# SUPPLY.net
KiCad netlist of a schematic drawn in Altium Designer
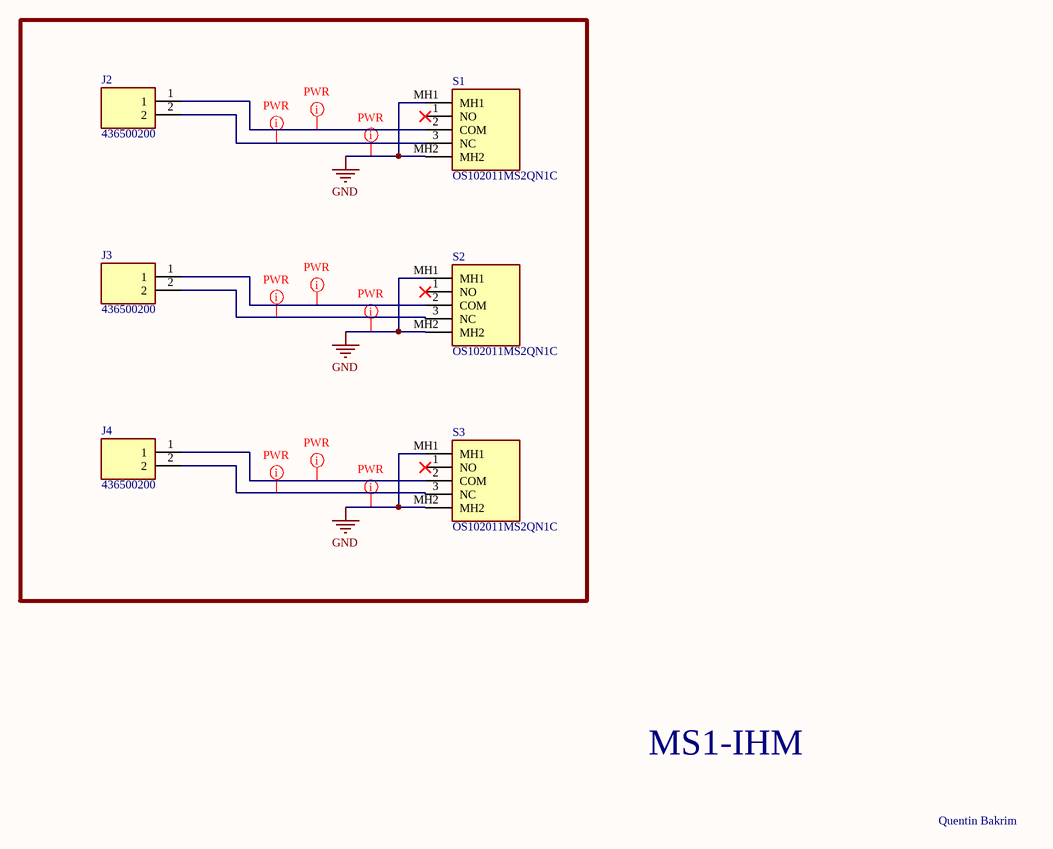
[diagram p0: SUPPLY.SchDoc]

(export (version "E")
  (design (tool "Eeschema 10.0.6"))
  (components
    (comp (ref "J2")
      (value "436500200")
      (footprint "436500200:MOLEX_436500200")
      (fields (field (name "MF") "{'manufacturer': u'Molex'}"))
      (libsource (lib "*") (part "436500200"))
    )
    (comp (ref "J3")
      (value "436500200")
      (footprint "436500200:MOLEX_436500200")
      (fields (field (name "MF") "{'manufacturer': u'Molex'}"))
      (libsource (lib "*") (part "436500200"))
    )
    (comp (ref "J4")
      (value "436500200")
      (footprint "436500200:MOLEX_436500200")
      (fields (field (name "MF") "{'manufacturer': u'Molex'}"))
      (libsource (lib "*") (part "436500200"))
    )
    (comp (ref "S1")
      (value "OS102011MS2QN1C")
      (footprint "SamacSys:OS102011MS2QN1C")
      (description "Switch")
      (fields (field (name "MOUSER PART NUMBER") "611-OS102011MS2QN1C"))
      (libsource (lib "*") (part "OS102011MS2QN1C"))
    )
    (comp (ref "S2")
      (value "OS102011MS2QN1C")
      (footprint "SamacSys:OS102011MS2QN1C")
      (description "Switch")
      (fields (field (name "MOUSER PART NUMBER") "611-OS102011MS2QN1C"))
      (libsource (lib "*") (part "OS102011MS2QN1C"))
    )
    (comp (ref "S3")
      (value "OS102011MS2QN1C")
      (footprint "SamacSys:OS102011MS2QN1C")
      (description "Switch")
      (fields (field (name "MOUSER PART NUMBER") "611-OS102011MS2QN1C"))
      (libsource (lib "*") (part "OS102011MS2QN1C"))
    )
  )
  (nets
    (net (code "1") (name "GND") (class "Default")
      (node (ref "S1") (pin "MH1") (pinfunction "MH1_MH1") (pintype "passive"))
      (node (ref "S1") (pin "MH2") (pinfunction "MH2_MH2") (pintype "passive"))
      (node (ref "S2") (pin "MH1") (pinfunction "MH1_MH1") (pintype "passive"))
      (node (ref "S2") (pin "MH2") (pinfunction "MH2_MH2") (pintype "passive"))
      (node (ref "S3") (pin "MH1") (pinfunction "MH1_MH1") (pintype "passive"))
      (node (ref "S3") (pin "MH2") (pinfunction "MH2_MH2") (pintype "passive"))
    )
    (net (code "2") (name "Net-(S1-COM)") (class "Default")
      (node (ref "J2") (pin "1") (pinfunction "1_1") (pintype "passive"))
      (node (ref "S1") (pin "2") (pinfunction "COM_2") (pintype "passive"))
    )
    (net (code "3") (name "Net-(S1-NC)") (class "Default")
      (node (ref "J2") (pin "2") (pinfunction "2_2") (pintype "passive"))
      (node (ref "S1") (pin "3") (pinfunction "NC_3") (pintype "passive"))
    )
    (net (code "4") (name "Net-(S2-COM)") (class "Default")
      (node (ref "J3") (pin "1") (pinfunction "1_1") (pintype "passive"))
      (node (ref "S2") (pin "2") (pinfunction "COM_2") (pintype "passive"))
    )
    (net (code "5") (name "Net-(S2-NC)") (class "Default")
      (node (ref "J3") (pin "2") (pinfunction "2_2") (pintype "passive"))
      (node (ref "S2") (pin "3") (pinfunction "NC_3") (pintype "passive"))
    )
    (net (code "6") (name "Net-(S3-COM)") (class "Default")
      (node (ref "J4") (pin "1") (pinfunction "1_1") (pintype "passive"))
      (node (ref "S3") (pin "2") (pinfunction "COM_2") (pintype "passive"))
    )
    (net (code "7") (name "Net-(S3-NC)") (class "Default")
      (node (ref "J4") (pin "2") (pinfunction "2_2") (pintype "passive"))
      (node (ref "S3") (pin "3") (pinfunction "NC_3") (pintype "passive"))
    )
    (net (code "8") (name "unconnected-(S1-NO-Pad1)") (class "Default")
      (node (ref "S1") (pin "1") (pinfunction "NO_1") (pintype "passive+no_connect"))
    )
    (net (code "9") (name "unconnected-(S2-NO-Pad1)") (class "Default")
      (node (ref "S2") (pin "1") (pinfunction "NO_1") (pintype "passive+no_connect"))
    )
    (net (code "10") (name "unconnected-(S3-NO-Pad1)") (class "Default")
      (node (ref "S3") (pin "1") (pinfunction "NO_1") (pintype "passive+no_connect"))
    )
  )
)
